# NODEMCU-ESP32-S2.net
KiCad netlist of a schematic drawn in Altium Designer
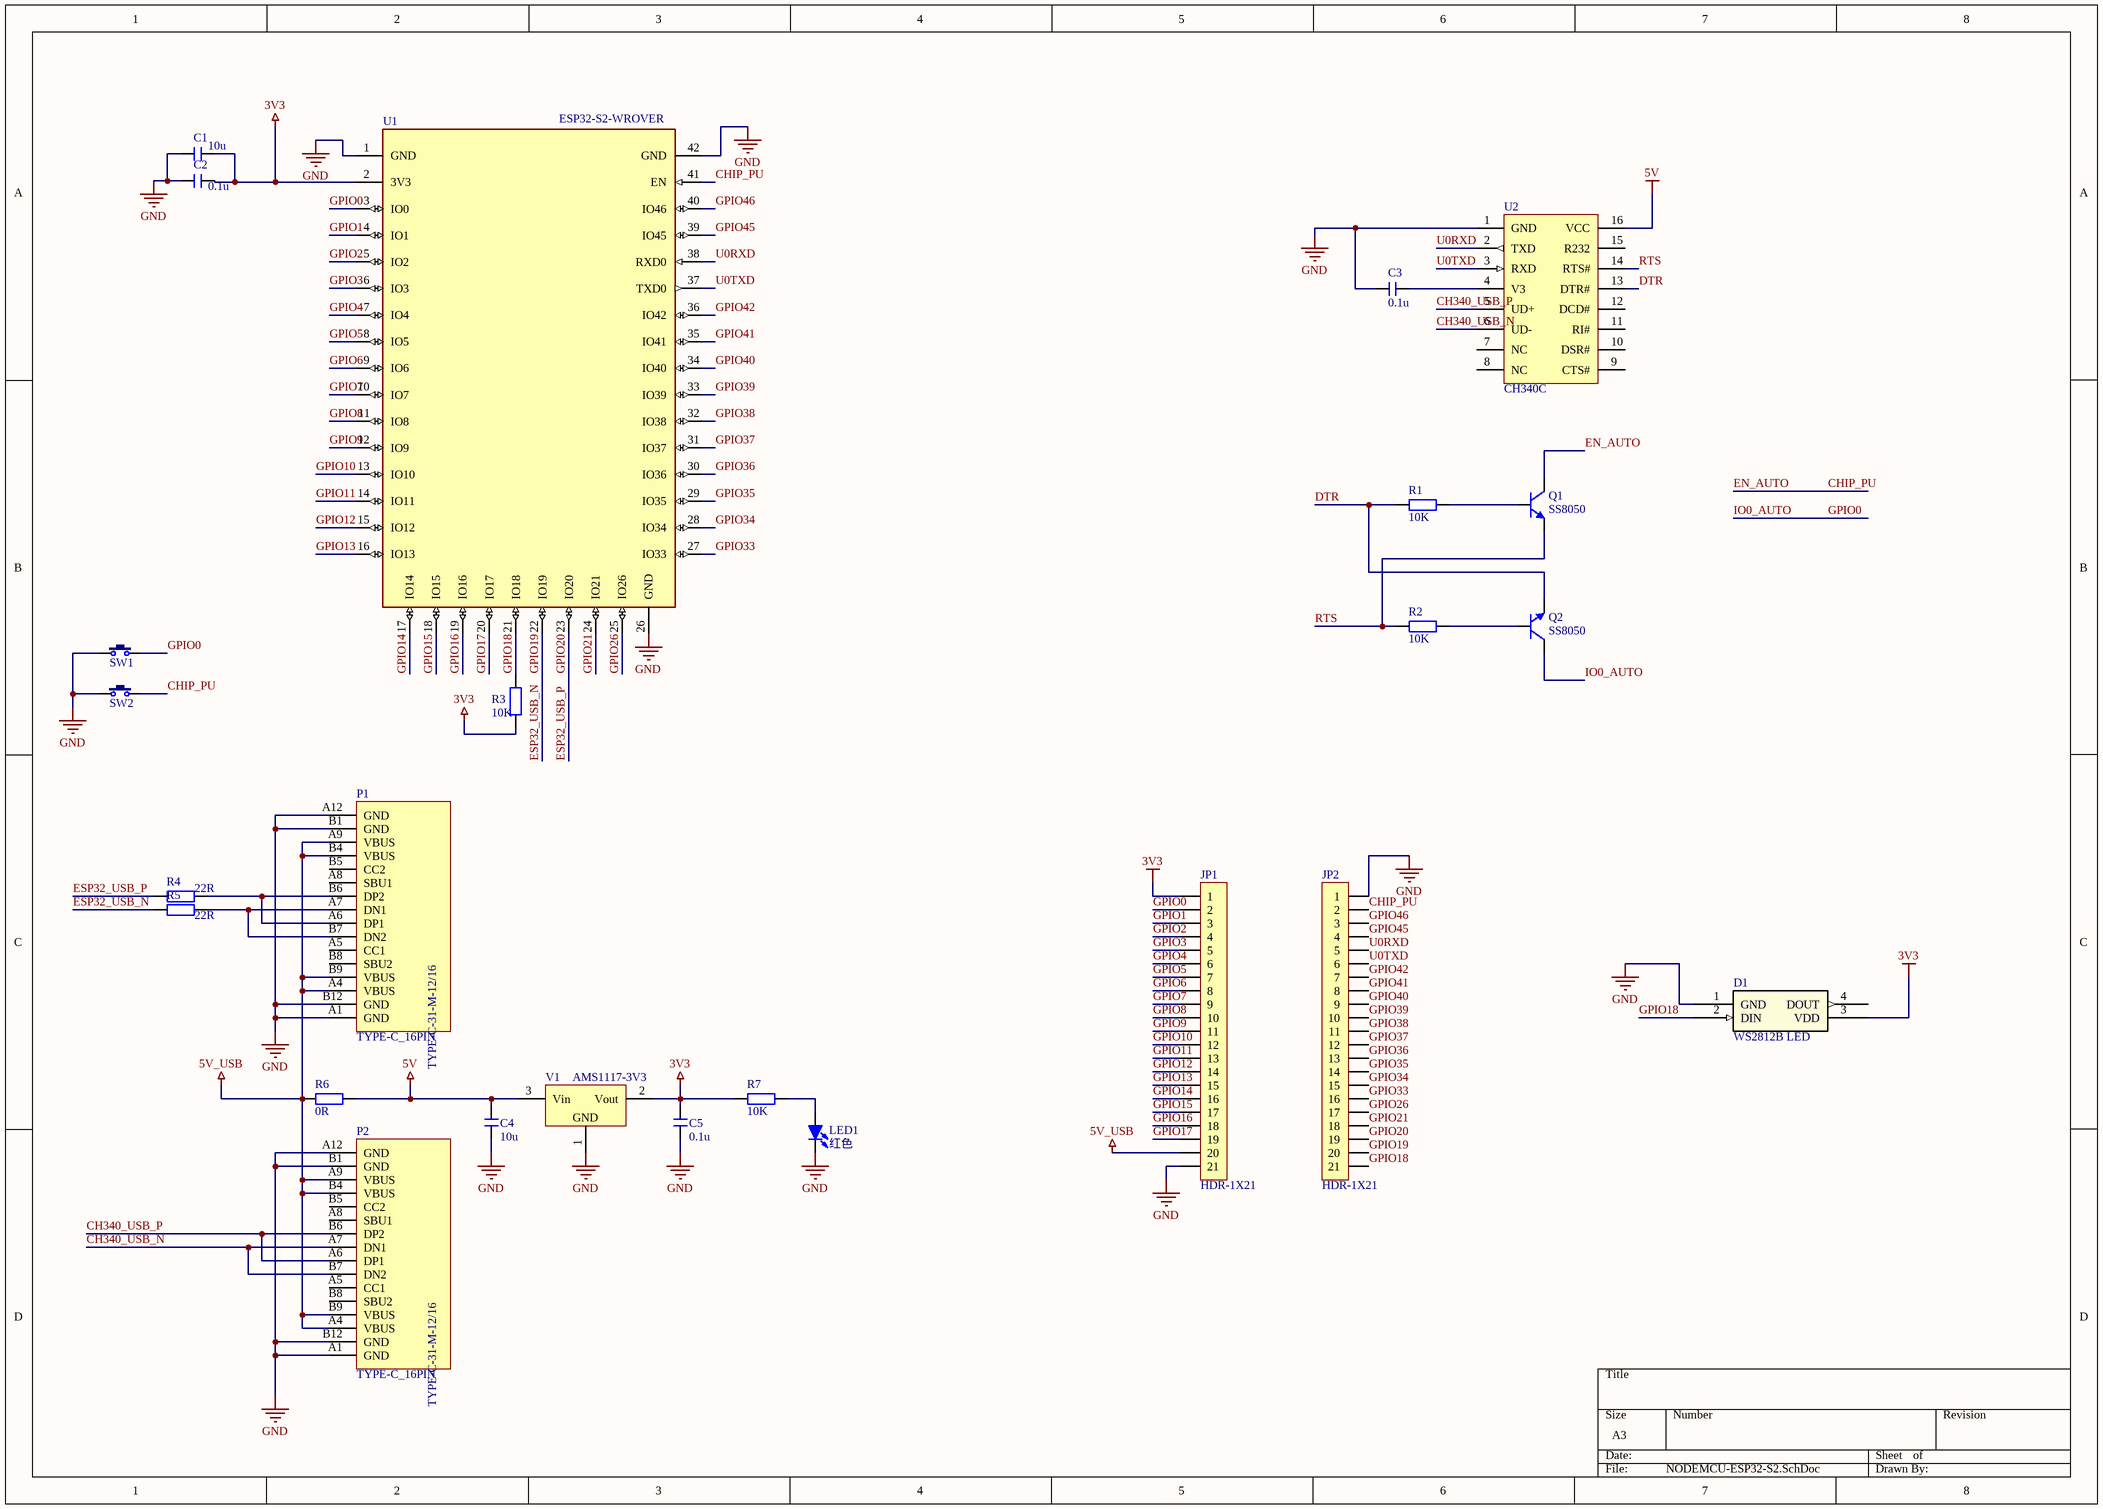
[diagram p0: NODEMCU-ESP32-S2.SchDoc]

(export (version "E")
  (design (tool "Eeschema 10.0.6"))
  (components
    (comp (ref "C1")
      (value "10u")
      (footprint "C 0603_M")
      (description "无极性贴片电容")
      (fields (field (name "版权归属") "源创客"))
      (libsource (lib "3.1   - 电阻-电容-电感") (part "C"))
    )
    (comp (ref "C2")
      (value "0.1u")
      (footprint "C 0603_M")
      (description "无极性贴片电容")
      (fields (field (name "版权归属") "源创客"))
      (libsource (lib "3.1   - 电阻-电容-电感") (part "C"))
    )
    (comp (ref "C3")
      (value "0.1u")
      (footprint "C 0603_M")
      (description "无极性贴片电容")
      (fields (field (name "版权归属") "源创客"))
      (libsource (lib "3.1   - 电阻-电容-电感") (part "C"))
    )
    (comp (ref "C4")
      (value "10u")
      (footprint "C 0603_M")
      (description "无极性贴片电容")
      (fields (field (name "版权归属") "源创客"))
      (libsource (lib "3.1   - 电阻-电容-电感") (part "C"))
    )
    (comp (ref "C5")
      (value "0.1u")
      (footprint "C 0603_M")
      (description "无极性贴片电容")
      (fields (field (name "版权归属") "源创客"))
      (libsource (lib "3.1   - 电阻-电容-电感") (part "C"))
    )
    (comp (ref "D1")
      (value "WS2812B LED")
      (footprint "WS2812B LED")
      (description "Imported")
      (fields (field (name "MANUFACTURER") "Texas Instruments") (field (name "GENERIC_PART_NUMBER") "OPA690"))
      (libsource (lib "WS2812B") (part "WS2812B LED"))
    )
    (comp (ref "JP1")
      (value "HDR-1X21")
      (footprint "HDR2.54-LI-21P")
      (description "21P接插件")
      (libsource (lib "4.5   - 接插件-脚距2.54") (part "Header 21"))
    )
    (comp (ref "JP2")
      (value "HDR-1X21")
      (footprint "HDR2.54-LI-21P")
      (description "21P接插件")
      (libsource (lib "") (part "Header 21_1"))
    )
    (comp (ref "LED1")
      (value "红色")
      (footprint "LED 0603R")
      (description "贴片LED")
      (fields (field (name "版权归属") "源创客"))
      (libsource (lib "9.1   - LED") (part "LED-SMD"))
    )
    (comp (ref "P1")
      (value "TYPE-C_16PIN")
      (footprint "USB-TYPE-C_16PIN")
      (fields (field (name "PUBLISHER") "Altium Limited"))
      (libsource (lib "TYPE-C-31-M-12_16") (part "TYPE-C_16PIN"))
    )
    (comp (ref "P2")
      (value "TYPE-C_16PIN")
      (footprint "USB-TYPE-C_16PIN")
      (fields (field (name "PUBLISHER") "Altium Limited"))
      (libsource (lib "TYPE-C-31-M-12_16") (part "TYPE-C_16PIN"))
    )
    (comp (ref "Q1")
      (value "SS8050")
      (footprint "SOT23-3N")
      (description "高频放大-NPN型")
      (fields (field (name "版权归属") "源创客"))
      (libsource (lib "6.2   - 三极管") (part "8050-SMD"))
    )
    (comp (ref "Q2")
      (value "SS8050")
      (footprint "SOT23-3N")
      (description "高频放大-NPN型")
      (fields (field (name "版权归属") "源创客"))
      (libsource (lib "6.2   - 三极管") (part "8050-SMD"))
    )
    (comp (ref "R1")
      (value "10K")
      (footprint "R 0603_M")
      (description "贴片电阻")
      (fields (field (name "版权归属") "源创客"))
      (libsource (lib "3.1   - 电阻-电容-电感") (part "R"))
    )
    (comp (ref "R2")
      (value "10K")
      (footprint "R 0603_M")
      (description "贴片电阻")
      (fields (field (name "版权归属") "源创客"))
      (libsource (lib "3.1   - 电阻-电容-电感") (part "R"))
    )
    (comp (ref "R3")
      (value "10K")
      (footprint "R 0603_M")
      (description "贴片电阻")
      (fields (field (name "版权归属") "源创客"))
      (libsource (lib "3.1   - 电阻-电容-电感") (part "R"))
    )
    (comp (ref "R4")
      (value "22R")
      (footprint "R 0603_M")
      (description "贴片电阻")
      (fields (field (name "版权归属") "源创客"))
      (libsource (lib "3.1   - 电阻-电容-电感") (part "R"))
    )
    (comp (ref "R5")
      (value "22R")
      (footprint "R 0603_M")
      (description "贴片电阻")
      (fields (field (name "版权归属") "源创客"))
      (libsource (lib "3.1   - 电阻-电容-电感") (part "R"))
    )
    (comp (ref "R6")
      (value "0R")
      (footprint "R 0805_M")
      (description "贴片电阻")
      (fields (field (name "版权归属") "源创客"))
      (libsource (lib "3.1   - 电阻-电容-电感") (part "R"))
    )
    (comp (ref "R7")
      (value "10K")
      (footprint "R 0603_M")
      (description "贴片电阻")
      (fields (field (name "版权归属") "源创客"))
      (libsource (lib "3.1   - 电阻-电容-电感") (part "R"))
    )
    (comp (ref "SW1")
      (value "3x6x5")
      (footprint "TSW SMD-3*6*2.5")
      (description "3x6轻触开关")
      (fields (field (name "版权归属") "源创客"))
      (libsource (lib "5.1   - 按键-开关") (part "TSW 3x6"))
    )
    (comp (ref "SW2")
      (value "3x6x5")
      (footprint "TSW SMD-3*6*2.5")
      (description "3x6轻触开关")
      (fields (field (name "版权归属") "源创客"))
      (libsource (lib "5.1   - 按键-开关") (part "TSW 3x6"))
    )
    (comp (ref "U1")
      (value "ESP32-S2-WROVER")
      (footprint "MODULE_ESP32-S2-WROVER:MODULE_ESP32-S2-WROVER")
      (fields (field (name "MF") "Espressif Systems") (field (name "MP") "ESP32-WROOM-32D"))
      (libsource (lib "MODULE_ESP32-S2-WROVER") (part "ESP32-S2-WROVER"))
    )
    (comp (ref "U2")
      (value "CH340C")
      (footprint "SOP16")
      (description "USB转串口 自带时钟")
      (fields (field (name "版权归属") "源创客"))
      (libsource (lib "CH340C") (part "CH340C"))
    )
    (comp (ref "V1")
      (value "AMS1117-3V3")
      (footprint "SOT223_L")
      (description "三端稳压芯片")
      (fields (field (name "版权归属") "源创客"))
      (libsource (lib "1.3   - 电源类芯片") (part "AMS1117"))
    )
  )
  (nets
    (net (code "1") (name "/CH340_USB_N") (class "Default")
      (node (ref "P2") (pin "A7") (pinfunction "DN1_A7") (pintype "passive"))
      (node (ref "P2") (pin "B7") (pinfunction "DN2_B7") (pintype "passive"))
      (node (ref "U2") (pin "6") (pinfunction "UD-_6") (pintype "passive"))
    )
    (net (code "2") (name "/CH340_USB_P") (class "Default")
      (node (ref "P2") (pin "A6") (pinfunction "DP1_A6") (pintype "passive"))
      (node (ref "P2") (pin "B6") (pinfunction "DP2_B6") (pintype "passive"))
      (node (ref "U2") (pin "5") (pinfunction "UD+_5") (pintype "passive"))
    )
    (net (code "3") (name "/CHIP_PU") (class "Default")
      (node (ref "JP2") (pin "2") (pinfunction "2_2") (pintype "passive"))
      (node (ref "Q1") (pin "3") (pinfunction "C_3") (pintype "passive"))
      (node (ref "SW2") (pin "2") (pinfunction "2_2") (pintype "passive"))
      (node (ref "U1") (pin "41") (pinfunction "EN_41") (pintype "input"))
    )
    (net (code "4") (name "/DTR") (class "Default")
      (node (ref "Q2") (pin "2") (pinfunction "E_2") (pintype "passive"))
      (node (ref "R1") (pin "1") (pinfunction "1_1") (pintype "passive"))
      (node (ref "U2") (pin "13") (pinfunction "DTR#_13") (pintype "passive"))
    )
    (net (code "5") (name "/ESP32_USB_N") (class "Default")
      (node (ref "JP2") (pin "20") (pinfunction "20_20") (pintype "passive"))
      (node (ref "R5") (pin "1") (pinfunction "1_1") (pintype "passive"))
      (node (ref "U1") (pin "22") (pinfunction "IO19_22") (pintype "bidirectional"))
    )
    (net (code "6") (name "/ESP32_USB_P") (class "Default")
      (node (ref "JP2") (pin "19") (pinfunction "19_19") (pintype "passive"))
      (node (ref "R4") (pin "1") (pinfunction "1_1") (pintype "passive"))
      (node (ref "U1") (pin "23") (pinfunction "IO20_23") (pintype "bidirectional"))
    )
    (net (code "7") (name "/GPIO0") (class "Default")
      (node (ref "JP1") (pin "2") (pinfunction "2_2") (pintype "passive"))
      (node (ref "Q2") (pin "3") (pinfunction "C_3") (pintype "passive"))
      (node (ref "SW1") (pin "2") (pinfunction "2_2") (pintype "passive"))
      (node (ref "U1") (pin "3") (pinfunction "IO0_3") (pintype "bidirectional"))
    )
    (net (code "8") (name "/GPIO1") (class "Default")
      (node (ref "JP1") (pin "3") (pinfunction "3_3") (pintype "passive"))
      (node (ref "U1") (pin "4") (pinfunction "IO1_4") (pintype "bidirectional"))
    )
    (net (code "9") (name "/GPIO2") (class "Default")
      (node (ref "JP1") (pin "4") (pinfunction "4_4") (pintype "passive"))
      (node (ref "U1") (pin "5") (pinfunction "IO2_5") (pintype "bidirectional"))
    )
    (net (code "10") (name "/GPIO3") (class "Default")
      (node (ref "JP1") (pin "5") (pinfunction "5_5") (pintype "passive"))
      (node (ref "U1") (pin "6") (pinfunction "IO3_6") (pintype "bidirectional"))
    )
    (net (code "11") (name "/GPIO4") (class "Default")
      (node (ref "JP1") (pin "6") (pinfunction "6_6") (pintype "passive"))
      (node (ref "U1") (pin "7") (pinfunction "IO4_7") (pintype "bidirectional"))
    )
    (net (code "12") (name "/GPIO5") (class "Default")
      (node (ref "JP1") (pin "7") (pinfunction "7_7") (pintype "passive"))
      (node (ref "U1") (pin "8") (pinfunction "IO5_8") (pintype "bidirectional"))
    )
    (net (code "13") (name "/GPIO6") (class "Default")
      (node (ref "JP1") (pin "8") (pinfunction "8_8") (pintype "passive"))
      (node (ref "U1") (pin "9") (pinfunction "IO6_9") (pintype "bidirectional"))
    )
    (net (code "14") (name "/GPIO7") (class "Default")
      (node (ref "JP1") (pin "9") (pinfunction "9_9") (pintype "passive"))
      (node (ref "U1") (pin "10") (pinfunction "IO7_10") (pintype "bidirectional"))
    )
    (net (code "15") (name "/GPIO8") (class "Default")
      (node (ref "JP1") (pin "10") (pinfunction "10_10") (pintype "passive"))
      (node (ref "U1") (pin "11") (pinfunction "IO8_11") (pintype "bidirectional"))
    )
    (net (code "16") (name "/GPIO9") (class "Default")
      (node (ref "JP1") (pin "11") (pinfunction "11_11") (pintype "passive"))
      (node (ref "U1") (pin "12") (pinfunction "IO9_12") (pintype "bidirectional"))
    )
    (net (code "17") (name "/GPIO10") (class "Default")
      (node (ref "JP1") (pin "12") (pinfunction "12_12") (pintype "passive"))
      (node (ref "U1") (pin "13") (pinfunction "IO10_13") (pintype "bidirectional"))
    )
    (net (code "18") (name "/GPIO11") (class "Default")
      (node (ref "JP1") (pin "13") (pinfunction "13_13") (pintype "passive"))
      (node (ref "U1") (pin "14") (pinfunction "IO11_14") (pintype "bidirectional"))
    )
    (net (code "19") (name "/GPIO12") (class "Default")
      (node (ref "JP1") (pin "14") (pinfunction "14_14") (pintype "passive"))
      (node (ref "U1") (pin "15") (pinfunction "IO12_15") (pintype "bidirectional"))
    )
    (net (code "20") (name "/GPIO13") (class "Default")
      (node (ref "JP1") (pin "15") (pinfunction "15_15") (pintype "passive"))
      (node (ref "U1") (pin "16") (pinfunction "IO13_16") (pintype "bidirectional"))
    )
    (net (code "21") (name "/GPIO14") (class "Default")
      (node (ref "JP1") (pin "16") (pinfunction "16_16") (pintype "passive"))
      (node (ref "U1") (pin "17") (pinfunction "IO14_17") (pintype "bidirectional"))
    )
    (net (code "22") (name "/GPIO15") (class "Default")
      (node (ref "JP1") (pin "17") (pinfunction "17_17") (pintype "passive"))
      (node (ref "U1") (pin "18") (pinfunction "IO15_18") (pintype "bidirectional"))
    )
    (net (code "23") (name "/GPIO16") (class "Default")
      (node (ref "JP1") (pin "18") (pinfunction "18_18") (pintype "passive"))
      (node (ref "U1") (pin "19") (pinfunction "IO16_19") (pintype "bidirectional"))
    )
    (net (code "24") (name "/GPIO17") (class "Default")
      (node (ref "JP1") (pin "19") (pinfunction "19_19") (pintype "passive"))
      (node (ref "U1") (pin "20") (pinfunction "IO17_20") (pintype "bidirectional"))
    )
    (net (code "25") (name "/GPIO18") (class "Default")
      (node (ref "D1") (pin "2") (pinfunction "DIN_2") (pintype "input"))
      (node (ref "JP2") (pin "21") (pinfunction "21_21") (pintype "passive"))
      (node (ref "R3") (pin "2") (pinfunction "2_2") (pintype "passive"))
      (node (ref "U1") (pin "21") (pinfunction "IO18_21") (pintype "bidirectional"))
    )
    (net (code "26") (name "/GPIO21") (class "Default")
      (node (ref "JP2") (pin "18") (pinfunction "18_18") (pintype "passive"))
      (node (ref "U1") (pin "24") (pinfunction "IO21_24") (pintype "bidirectional"))
    )
    (net (code "27") (name "/GPIO26") (class "Default")
      (node (ref "JP2") (pin "17") (pinfunction "17_17") (pintype "passive"))
      (node (ref "U1") (pin "25") (pinfunction "IO26_25") (pintype "bidirectional"))
    )
    (net (code "28") (name "/GPIO33") (class "Default")
      (node (ref "JP2") (pin "16") (pinfunction "16_16") (pintype "passive"))
      (node (ref "U1") (pin "27") (pinfunction "IO33_27") (pintype "bidirectional"))
    )
    (net (code "29") (name "/GPIO34") (class "Default")
      (node (ref "JP2") (pin "15") (pinfunction "15_15") (pintype "passive"))
      (node (ref "U1") (pin "28") (pinfunction "IO34_28") (pintype "bidirectional"))
    )
    (net (code "30") (name "/GPIO35") (class "Default")
      (node (ref "JP2") (pin "14") (pinfunction "14_14") (pintype "passive"))
      (node (ref "U1") (pin "29") (pinfunction "IO35_29") (pintype "bidirectional"))
    )
    (net (code "31") (name "/GPIO36") (class "Default")
      (node (ref "JP2") (pin "13") (pinfunction "13_13") (pintype "passive"))
      (node (ref "U1") (pin "30") (pinfunction "IO36_30") (pintype "bidirectional"))
    )
    (net (code "32") (name "/GPIO37") (class "Default")
      (node (ref "JP2") (pin "12") (pinfunction "12_12") (pintype "passive"))
      (node (ref "U1") (pin "31") (pinfunction "IO37_31") (pintype "bidirectional"))
    )
    (net (code "33") (name "/GPIO38") (class "Default")
      (node (ref "JP2") (pin "11") (pinfunction "11_11") (pintype "passive"))
      (node (ref "U1") (pin "32") (pinfunction "IO38_32") (pintype "bidirectional"))
    )
    (net (code "34") (name "/GPIO39") (class "Default")
      (node (ref "JP2") (pin "10") (pinfunction "10_10") (pintype "passive"))
      (node (ref "U1") (pin "33") (pinfunction "IO39_33") (pintype "bidirectional"))
    )
    (net (code "35") (name "/GPIO40") (class "Default")
      (node (ref "JP2") (pin "9") (pinfunction "9_9") (pintype "passive"))
      (node (ref "U1") (pin "34") (pinfunction "IO40_34") (pintype "bidirectional"))
    )
    (net (code "36") (name "/GPIO41") (class "Default")
      (node (ref "JP2") (pin "8") (pinfunction "8_8") (pintype "passive"))
      (node (ref "U1") (pin "35") (pinfunction "IO41_35") (pintype "bidirectional"))
    )
    (net (code "37") (name "/GPIO42") (class "Default")
      (node (ref "JP2") (pin "7") (pinfunction "7_7") (pintype "passive"))
      (node (ref "U1") (pin "36") (pinfunction "IO42_36") (pintype "bidirectional"))
    )
    (net (code "38") (name "/GPIO45") (class "Default")
      (node (ref "JP2") (pin "4") (pinfunction "4_4") (pintype "passive"))
      (node (ref "U1") (pin "39") (pinfunction "IO45_39") (pintype "bidirectional"))
    )
    (net (code "39") (name "/GPIO46") (class "Default")
      (node (ref "JP2") (pin "3") (pinfunction "3_3") (pintype "passive"))
      (node (ref "U1") (pin "40") (pinfunction "IO46_40") (pintype "bidirectional"))
    )
    (net (code "40") (name "/RTS") (class "Default")
      (node (ref "Q1") (pin "2") (pinfunction "E_2") (pintype "passive"))
      (node (ref "R2") (pin "1") (pinfunction "1_1") (pintype "passive"))
      (node (ref "U2") (pin "14") (pinfunction "RTS#_14") (pintype "passive"))
    )
    (net (code "41") (name "/U0RXD") (class "Default")
      (node (ref "JP2") (pin "5") (pinfunction "5_5") (pintype "passive"))
      (node (ref "U1") (pin "38") (pinfunction "RXD0_38") (pintype "input"))
      (node (ref "U2") (pin "2") (pinfunction "TXD_2") (pintype "output"))
    )
    (net (code "42") (name "/U0TXD") (class "Default")
      (node (ref "JP2") (pin "6") (pinfunction "6_6") (pintype "passive"))
      (node (ref "U1") (pin "37") (pinfunction "TXD0_37") (pintype "output"))
      (node (ref "U2") (pin "3") (pinfunction "RXD_3") (pintype "input"))
    )
    (net (code "43") (name "3V3") (class "Default")
      (node (ref "C1") (pin "1") (pinfunction "1_1") (pintype "passive"))
      (node (ref "C2") (pin "2") (pinfunction "2_2") (pintype "passive"))
      (node (ref "C5") (pin "2") (pinfunction "2_2") (pintype "passive"))
      (node (ref "D1") (pin "3") (pinfunction "VDD_3") (pintype "power_in"))
      (node (ref "JP1") (pin "1") (pinfunction "1_1") (pintype "passive"))
      (node (ref "R3") (pin "1") (pinfunction "1_1") (pintype "passive"))
      (node (ref "R7") (pin "2") (pinfunction "2_2") (pintype "passive"))
      (node (ref "U1") (pin "2") (pinfunction "3V3_2") (pintype "power_in"))
      (node (ref "V1") (pin "2") (pinfunction "Vout_2") (pintype "passive"))
    )
    (net (code "44") (name "5V") (class "Default")
      (node (ref "C4") (pin "2") (pinfunction "2_2") (pintype "passive"))
      (node (ref "R6") (pin "2") (pinfunction "2_2") (pintype "passive"))
      (node (ref "U2") (pin "16") (pinfunction "VCC_16") (pintype "power_in"))
      (node (ref "V1") (pin "3") (pinfunction "Vin_3") (pintype "passive"))
    )
    (net (code "45") (name "5V_USB") (class "Default")
      (node (ref "JP1") (pin "20") (pinfunction "20_20") (pintype "passive"))
      (node (ref "P1") (pin "A4") (pinfunction "VBUS_A4") (pintype "passive"))
      (node (ref "P1") (pin "A9") (pinfunction "VBUS_A9") (pintype "passive"))
      (node (ref "P1") (pin "B4") (pinfunction "VBUS_B4") (pintype "passive"))
      (node (ref "P1") (pin "B9") (pinfunction "VBUS_B9") (pintype "passive"))
      (node (ref "P2") (pin "A4") (pinfunction "VBUS_A4") (pintype "passive"))
      (node (ref "P2") (pin "A9") (pinfunction "VBUS_A9") (pintype "passive"))
      (node (ref "P2") (pin "B4") (pinfunction "VBUS_B4") (pintype "passive"))
      (node (ref "P2") (pin "B9") (pinfunction "VBUS_B9") (pintype "passive"))
      (node (ref "R6") (pin "1") (pinfunction "1_1") (pintype "passive"))
    )
    (net (code "46") (name "GND") (class "Default")
      (node (ref "C1") (pin "2") (pinfunction "2_2") (pintype "passive"))
      (node (ref "C2") (pin "1") (pinfunction "1_1") (pintype "passive"))
      (node (ref "C3") (pin "1") (pinfunction "1_1") (pintype "passive"))
      (node (ref "C4") (pin "1") (pinfunction "1_1") (pintype "passive"))
      (node (ref "C5") (pin "1") (pinfunction "1_1") (pintype "passive"))
      (node (ref "D1") (pin "1") (pinfunction "GND_1") (pintype "power_in"))
      (node (ref "JP1") (pin "21") (pinfunction "21_21") (pintype "passive"))
      (node (ref "JP2") (pin "1") (pinfunction "1_1") (pintype "passive"))
      (node (ref "LED1") (pin "2") (pinfunction "K_2") (pintype "passive"))
      (node (ref "P1") (pin "A1") (pinfunction "GND_A1") (pintype "passive"))
      (node (ref "P1") (pin "A12") (pinfunction "GND_A12") (pintype "passive"))
      (node (ref "P1") (pin "B1") (pinfunction "GND_B1") (pintype "passive"))
      (node (ref "P1") (pin "B12") (pinfunction "GND_B12") (pintype "passive"))
      (node (ref "P2") (pin "A1") (pinfunction "GND_A1") (pintype "passive"))
      (node (ref "P2") (pin "A12") (pinfunction "GND_A12") (pintype "passive"))
      (node (ref "P2") (pin "B1") (pinfunction "GND_B1") (pintype "passive"))
      (node (ref "P2") (pin "B12") (pinfunction "GND_B12") (pintype "passive"))
      (node (ref "SW1") (pin "1") (pinfunction "1_1") (pintype "passive"))
      (node (ref "SW2") (pin "1") (pinfunction "1_1") (pintype "passive"))
      (node (ref "U1") (pin "1") (pinfunction "GND_1") (pintype "power_in"))
      (node (ref "U1") (pin "26") (pinfunction "GND_26") (pintype "power_in"))
      (node (ref "U1") (pin "42") (pinfunction "GND_42") (pintype "power_in"))
      (node (ref "U2") (pin "1") (pinfunction "GND_1") (pintype "power_in"))
      (node (ref "V1") (pin "1") (pinfunction "GND_1") (pintype "passive"))
    )
    (net (code "47") (name "Net-(LED1-A)") (class "Default")
      (node (ref "LED1") (pin "1") (pinfunction "A_1") (pintype "passive"))
      (node (ref "R7") (pin "1") (pinfunction "1_1") (pintype "passive"))
    )
    (net (code "48") (name "Net-(P1-DN1)") (class "Default")
      (node (ref "P1") (pin "A7") (pinfunction "DN1_A7") (pintype "passive"))
      (node (ref "P1") (pin "B7") (pinfunction "DN2_B7") (pintype "passive"))
      (node (ref "R5") (pin "2") (pinfunction "2_2") (pintype "passive"))
    )
    (net (code "49") (name "Net-(P1-DP1)") (class "Default")
      (node (ref "P1") (pin "A6") (pinfunction "DP1_A6") (pintype "passive"))
      (node (ref "P1") (pin "B6") (pinfunction "DP2_B6") (pintype "passive"))
      (node (ref "R4") (pin "2") (pinfunction "2_2") (pintype "passive"))
    )
    (net (code "50") (name "Net-(Q1-B)") (class "Default")
      (node (ref "Q1") (pin "1") (pinfunction "B_1") (pintype "passive"))
      (node (ref "R1") (pin "2") (pinfunction "2_2") (pintype "passive"))
    )
    (net (code "51") (name "Net-(Q2-B)") (class "Default")
      (node (ref "Q2") (pin "1") (pinfunction "B_1") (pintype "passive"))
      (node (ref "R2") (pin "2") (pinfunction "2_2") (pintype "passive"))
    )
    (net (code "52") (name "Net-(U2-V3)") (class "Default")
      (node (ref "C3") (pin "2") (pinfunction "2_2") (pintype "passive"))
      (node (ref "U2") (pin "4") (pinfunction "V3_4") (pintype "passive"))
    )
    (net (code "53") (name "unconnected-(D1-DOUT-Pad4)") (class "Default")
      (node (ref "D1") (pin "4") (pinfunction "DOUT_4") (pintype "output"))
    )
    (net (code "54") (name "unconnected-(P1-CC1-PadA5)") (class "Default")
      (node (ref "P1") (pin "A5") (pinfunction "CC1_A5") (pintype "passive"))
    )
    (net (code "55") (name "unconnected-(P1-CC2-PadB5)") (class "Default")
      (node (ref "P1") (pin "B5") (pinfunction "CC2_B5") (pintype "passive"))
    )
    (net (code "56") (name "unconnected-(P1-SBU1-PadA8)") (class "Default")
      (node (ref "P1") (pin "A8") (pinfunction "SBU1_A8") (pintype "passive"))
    )
    (net (code "57") (name "unconnected-(P1-SBU2-PadB8)") (class "Default")
      (node (ref "P1") (pin "B8") (pinfunction "SBU2_B8") (pintype "passive"))
    )
    (net (code "58") (name "unconnected-(P2-CC1-PadA5)") (class "Default")
      (node (ref "P2") (pin "A5") (pinfunction "CC1_A5") (pintype "passive"))
    )
    (net (code "59") (name "unconnected-(P2-CC2-PadB5)") (class "Default")
      (node (ref "P2") (pin "B5") (pinfunction "CC2_B5") (pintype "passive"))
    )
    (net (code "60") (name "unconnected-(P2-SBU1-PadA8)") (class "Default")
      (node (ref "P2") (pin "A8") (pinfunction "SBU1_A8") (pintype "passive"))
    )
    (net (code "61") (name "unconnected-(P2-SBU2-PadB8)") (class "Default")
      (node (ref "P2") (pin "B8") (pinfunction "SBU2_B8") (pintype "passive"))
    )
    (net (code "62") (name "unconnected-(U2-CTS#-Pad9)") (class "Default")
      (node (ref "U2") (pin "9") (pinfunction "CTS#_9") (pintype "passive"))
    )
    (net (code "63") (name "unconnected-(U2-DCD#-Pad12)") (class "Default")
      (node (ref "U2") (pin "12") (pinfunction "DCD#_12") (pintype "passive"))
    )
    (net (code "64") (name "unconnected-(U2-DSR#-Pad10)") (class "Default")
      (node (ref "U2") (pin "10") (pinfunction "DSR#_10") (pintype "passive"))
    )
    (net (code "65") (name "unconnected-(U2-NC-Pad7)") (class "Default")
      (node (ref "U2") (pin "7") (pinfunction "NC_7") (pintype "passive"))
    )
    (net (code "66") (name "unconnected-(U2-NC-Pad8)") (class "Default")
      (node (ref "U2") (pin "8") (pinfunction "NC_8") (pintype "passive"))
    )
    (net (code "67") (name "unconnected-(U2-R232-Pad15)") (class "Default")
      (node (ref "U2") (pin "15") (pinfunction "R232_15") (pintype "passive"))
    )
    (net (code "68") (name "unconnected-(U2-RI#-Pad11)") (class "Default")
      (node (ref "U2") (pin "11") (pinfunction "RI#_11") (pintype "passive"))
    )
  )
)
